# ai_esp12e_aerial.net
KiCad netlist of a schematic drawn in EAGLE
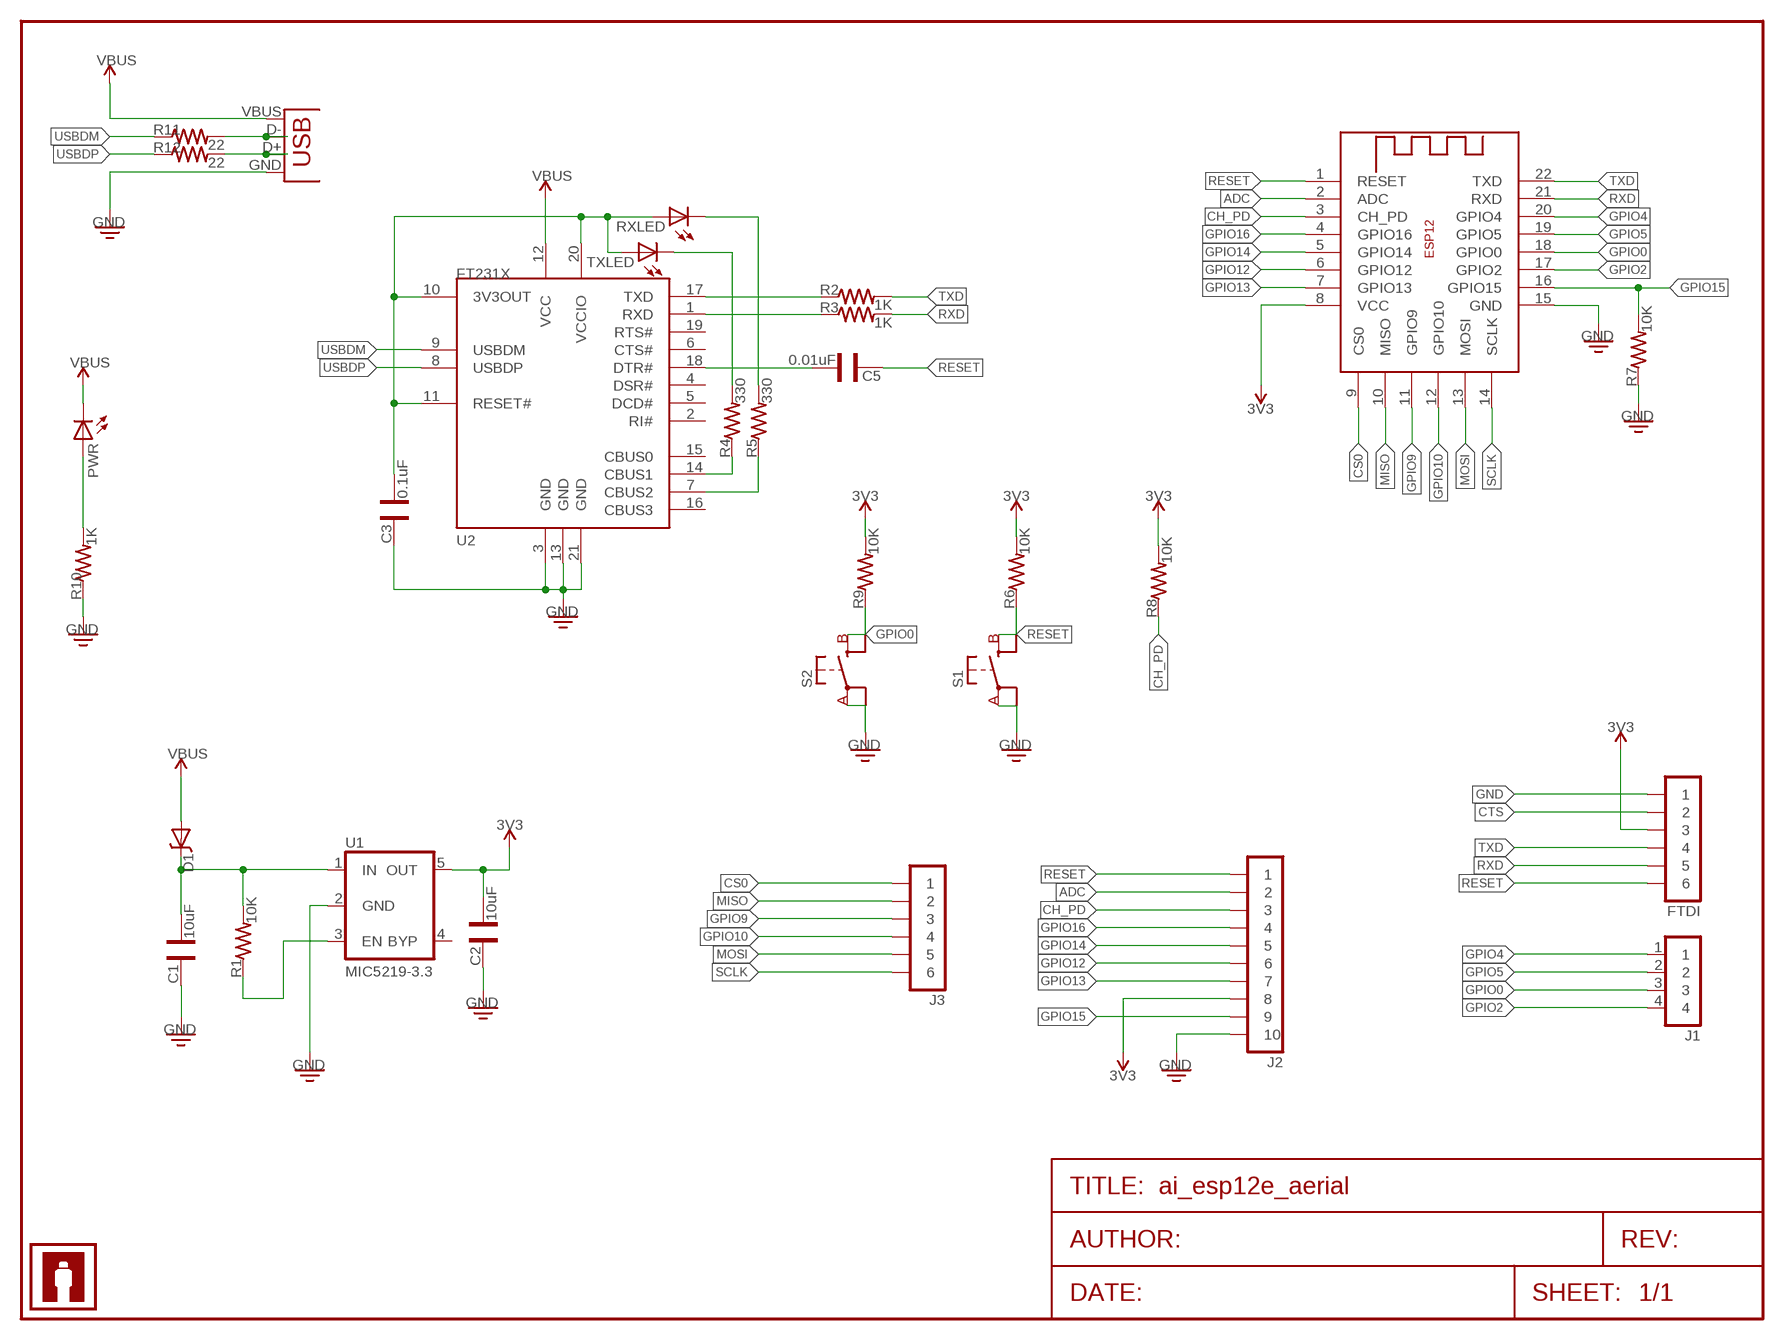
[diagram p0: schematic, sheet 1]

(export (version "E")
  (design (tool "Eeschema 10.0.6"))
  (components
    (comp (ref "C1")
      (value "10uF")
      (footprint "eagle-import:CAP-0603")
      (libsource (lib "eagle-import") (part "CAP0603"))
    )
    (comp (ref "C2")
      (value "10uF")
      (footprint "eagle-import:CAP-0603")
      (libsource (lib "eagle-import") (part "CAP0603"))
    )
    (comp (ref "C3")
      (value "0.1uF")
      (footprint "eagle-import:CAP-0603")
      (libsource (lib "eagle-import") (part "CAP0603"))
    )
    (comp (ref "C5")
      (value "0.01uF")
      (footprint "eagle-import:CAP-0603")
      (libsource (lib "eagle-import") (part "CAP0603"))
    )
    (comp (ref "D1")
      (value "DIODE-SCHOTTKYSOD-523")
      (footprint "eagle-import:SOD-523")
      (libsource (lib "eagle-import") (part "DIODE-SCHOTTKYSOD-523"))
    )
    (comp (ref "FTDI")
      (value "1X06FTDI")
      (footprint "eagle-import:1X06-CUSTOMSP")
      (libsource (lib "eagle-import") (part "1X06FTDI"))
    )
    (comp (ref "J1")
      (value "1X04NFNS")
      (footprint "eagle-import:1X04-NFNS")
      (libsource (lib "eagle-import") (part "1X04NFNS"))
    )
    (comp (ref "J2")
      (value "1X10NFNS")
      (footprint "eagle-import:1X10-NFNS")
      (libsource (lib "eagle-import") (part "1X10NFNS"))
    )
    (comp (ref "J3")
      (value "1X061X06-NFNS")
      (footprint "eagle-import:1X06-NFNS")
      (libsource (lib "eagle-import") (part "1X061X06-NFNS"))
    )
    (comp (ref "PWR")
      (value "LED0603")
      (footprint "eagle-import:LED-0603")
      (libsource (lib "eagle-import") (part "LED0603"))
    )
    (comp (ref "R1")
      (value "10K")
      (footprint "eagle-import:RES-0603")
      (libsource (lib "eagle-import") (part "RES0603"))
    )
    (comp (ref "R2")
      (value "1K")
      (footprint "eagle-import:RES-0603")
      (libsource (lib "eagle-import") (part "RES0603"))
    )
    (comp (ref "R3")
      (value "1K")
      (footprint "eagle-import:RES-0603")
      (libsource (lib "eagle-import") (part "RES0603"))
    )
    (comp (ref "R4")
      (value "330")
      (footprint "eagle-import:RES-0603")
      (libsource (lib "eagle-import") (part "RES0603"))
    )
    (comp (ref "R5")
      (value "330")
      (footprint "eagle-import:RES-0603")
      (libsource (lib "eagle-import") (part "RES0603"))
    )
    (comp (ref "R6")
      (value "10K")
      (footprint "eagle-import:RES-0603")
      (libsource (lib "eagle-import") (part "RES0603"))
    )
    (comp (ref "R7")
      (value "10K")
      (footprint "eagle-import:RES-0603")
      (libsource (lib "eagle-import") (part "RES0603"))
    )
    (comp (ref "R8")
      (value "10K")
      (footprint "eagle-import:RES-0603")
      (libsource (lib "eagle-import") (part "RES0603"))
    )
    (comp (ref "R9")
      (value "10K")
      (footprint "eagle-import:RES-0603")
      (libsource (lib "eagle-import") (part "RES0603"))
    )
    (comp (ref "R10")
      (value "1K")
      (footprint "eagle-import:RES-0603")
      (libsource (lib "eagle-import") (part "RES0603"))
    )
    (comp (ref "R11")
      (value "22")
      (footprint "eagle-import:RES-0603")
      (libsource (lib "eagle-import") (part "RES0603"))
    )
    (comp (ref "R12")
      (value "22")
      (footprint "eagle-import:RES-0603")
      (libsource (lib "eagle-import") (part "RES0603"))
    )
    (comp (ref "RXLED")
      (value "LED0603")
      (footprint "eagle-import:LED-0603")
      (libsource (lib "eagle-import") (part "LED0603"))
    )
    (comp (ref "S1")
      (value "SW-SPSTSMD06X035")
      (footprint "eagle-import:SW-SPST-SMD06X-035")
      (libsource (lib "eagle-import") (part "SW-SPSTSMD06X035"))
    )
    (comp (ref "S2")
      (value "SW-SPSTSMD06X035")
      (footprint "eagle-import:SW-SPST-SMD06X-035")
      (libsource (lib "eagle-import") (part "SW-SPSTSMD06X035"))
    )
    (comp (ref "TXLED")
      (value "LED0603")
      (footprint "eagle-import:LED-0603")
      (libsource (lib "eagle-import") (part "LED0603"))
    )
    (comp (ref "U$1")
      (value "AI-LOGOXS")
      (footprint "eagle-import:AI-LOGO-XS")
      (libsource (lib "eagle-import") (part "AI-LOGOXS"))
    )
    (comp (ref "U1")
      (value "MIC5219-3.3")
      (footprint "eagle-import:SOT23-5")
      (libsource (lib "eagle-import") (part "MIC5219-3.3"))
    )
    (comp (ref "U2")
      (value "FT231X-Q")
      (footprint "eagle-import:QFN20")
      (libsource (lib "eagle-import") (part "FT231X-Q"))
    )
    (comp (ref "USB1")
      (value "USBMICROB-TH")
      (footprint "eagle-import:USB-MICROB-TH")
      (libsource (lib "eagle-import") (part "USBMICROB-TH"))
    )
    (comp (ref "X1")
      (value "ESP-12")
      (footprint "eagle-import:ESP-12")
      (libsource (lib "eagle-import") (part "ESP-12"))
    )
  )
  (nets
    (net (code "1") (name "3V3") (class "Default")
      (node (ref "C2") (pin "1") (pinfunction "1_1") (pintype "passive"))
      (node (ref "FTDI") (pin "3") (pinfunction "3_3") (pintype "bidirectional"))
      (node (ref "J2") (pin "8") (pinfunction "8_8") (pintype "bidirectional"))
      (node (ref "R6") (pin "2") (pinfunction "2_2") (pintype "passive"))
      (node (ref "R8") (pin "2") (pinfunction "2_2") (pintype "passive"))
      (node (ref "R9") (pin "2") (pinfunction "2_2") (pintype "passive"))
      (node (ref "U1") (pin "5") (pinfunction "OUT_5") (pintype "passive"))
      (node (ref "X1") (pin "8") (pinfunction "VCC_8") (pintype "power_in"))
    )
    (net (code "2") (name "ADC") (class "Default")
      (node (ref "J2") (pin "2") (pinfunction "2_2") (pintype "bidirectional"))
      (node (ref "X1") (pin "2") (pinfunction "ADC_2") (pintype "passive"))
    )
    (net (code "3") (name "CH_PD") (class "Default")
      (node (ref "J2") (pin "3") (pinfunction "3_3") (pintype "bidirectional"))
      (node (ref "R8") (pin "1") (pinfunction "1_1") (pintype "passive"))
      (node (ref "X1") (pin "3") (pinfunction "CH_PD_3") (pintype "input"))
    )
    (net (code "4") (name "CS0") (class "Default")
      (node (ref "J3") (pin "1") (pinfunction "1_1") (pintype "bidirectional"))
      (node (ref "X1") (pin "9") (pinfunction "CS0_9") (pintype "bidirectional"))
    )
    (net (code "5") (name "CTS") (class "Default")
      (node (ref "FTDI") (pin "2") (pinfunction "2_2") (pintype "bidirectional"))
    )
    (net (code "6") (name "GND") (class "Default")
      (node (ref "C1") (pin "2") (pinfunction "2_2") (pintype "passive"))
      (node (ref "C2") (pin "2") (pinfunction "2_2") (pintype "passive"))
      (node (ref "C3") (pin "2") (pinfunction "2_2") (pintype "passive"))
      (node (ref "FTDI") (pin "1") (pinfunction "1_1") (pintype "bidirectional"))
      (node (ref "J2") (pin "10") (pinfunction "10_10") (pintype "bidirectional"))
      (node (ref "R10") (pin "1") (pinfunction "1_1") (pintype "passive"))
      (node (ref "R7") (pin "1") (pinfunction "1_1") (pintype "passive"))
      (node (ref "S1") (pin "P$1") (pinfunction "A_P$1") (pintype "passive"))
      (node (ref "S2") (pin "P$1") (pinfunction "A_P$1") (pintype "passive"))
      (node (ref "U1") (pin "2") (pinfunction "GND_2") (pintype "input"))
      (node (ref "U2") (pin "13") (pinfunction "GND_13") (pintype "bidirectional"))
      (node (ref "U2") (pin "21") (pinfunction "GND_21") (pintype "bidirectional"))
      (node (ref "U2") (pin "3") (pinfunction "GND_3") (pintype "bidirectional"))
      (node (ref "USB1") (pin "GND") (pinfunction "GND_GND") (pintype "bidirectional"))
      (node (ref "X1") (pin "15") (pinfunction "GND_15") (pintype "power_in"))
    )
    (net (code "7") (name "GPIO0") (class "Default")
      (node (ref "J1") (pin "3") (pinfunction "3_3") (pintype "bidirectional"))
      (node (ref "R9") (pin "1") (pinfunction "1_1") (pintype "passive"))
      (node (ref "S2") (pin "P$2") (pinfunction "B_P$2") (pintype "passive"))
      (node (ref "X1") (pin "18") (pinfunction "GPIO0_18") (pintype "bidirectional"))
    )
    (net (code "8") (name "GPIO2") (class "Default")
      (node (ref "J1") (pin "4") (pinfunction "4_4") (pintype "bidirectional"))
      (node (ref "X1") (pin "17") (pinfunction "GPIO2_17") (pintype "bidirectional"))
    )
    (net (code "9") (name "GPIO4") (class "Default")
      (node (ref "J1") (pin "1") (pinfunction "1_1") (pintype "bidirectional"))
      (node (ref "X1") (pin "20") (pinfunction "GPIO4_20") (pintype "bidirectional"))
    )
    (net (code "10") (name "GPIO5") (class "Default")
      (node (ref "J1") (pin "2") (pinfunction "2_2") (pintype "bidirectional"))
      (node (ref "X1") (pin "19") (pinfunction "GPIO5_19") (pintype "bidirectional"))
    )
    (net (code "11") (name "GPIO9") (class "Default")
      (node (ref "J3") (pin "3") (pinfunction "3_3") (pintype "bidirectional"))
      (node (ref "X1") (pin "11") (pinfunction "GPIO9_11") (pintype "bidirectional"))
    )
    (net (code "12") (name "GPIO10") (class "Default")
      (node (ref "J3") (pin "4") (pinfunction "4_4") (pintype "bidirectional"))
      (node (ref "X1") (pin "12") (pinfunction "GPIO10_12") (pintype "bidirectional"))
    )
    (net (code "13") (name "GPIO12") (class "Default")
      (node (ref "J2") (pin "6") (pinfunction "6_6") (pintype "bidirectional"))
      (node (ref "X1") (pin "6") (pinfunction "GPIO12_6") (pintype "bidirectional"))
    )
    (net (code "14") (name "GPIO13") (class "Default")
      (node (ref "J2") (pin "7") (pinfunction "7_7") (pintype "bidirectional"))
      (node (ref "X1") (pin "7") (pinfunction "GPIO13_7") (pintype "bidirectional"))
    )
    (net (code "15") (name "GPIO14") (class "Default")
      (node (ref "J2") (pin "5") (pinfunction "5_5") (pintype "bidirectional"))
      (node (ref "X1") (pin "5") (pinfunction "GPIO14_5") (pintype "bidirectional"))
    )
    (net (code "16") (name "GPIO15") (class "Default")
      (node (ref "J2") (pin "9") (pinfunction "9_9") (pintype "bidirectional"))
      (node (ref "R7") (pin "2") (pinfunction "2_2") (pintype "passive"))
      (node (ref "X1") (pin "16") (pinfunction "GPIO15_16") (pintype "bidirectional"))
    )
    (net (code "17") (name "GPIO16") (class "Default")
      (node (ref "J2") (pin "4") (pinfunction "4_4") (pintype "bidirectional"))
      (node (ref "X1") (pin "4") (pinfunction "GPIO16_4") (pintype "bidirectional"))
    )
    (net (code "18") (name "MISO") (class "Default")
      (node (ref "J3") (pin "2") (pinfunction "2_2") (pintype "bidirectional"))
      (node (ref "X1") (pin "10") (pinfunction "MISO_10") (pintype "bidirectional"))
    )
    (net (code "19") (name "MOSI") (class "Default")
      (node (ref "J3") (pin "5") (pinfunction "5_5") (pintype "bidirectional"))
      (node (ref "X1") (pin "13") (pinfunction "MOSI_13") (pintype "bidirectional"))
    )
    (net (code "20") (name "Net-(PWR-PadA)") (class "Default")
      (node (ref "PWR") (pin "A") (pinfunction "A_A") (pintype "passive"))
      (node (ref "R10") (pin "2") (pinfunction "2_2") (pintype "passive"))
    )
    (net (code "21") (name "Net-(R4-Pad2)") (class "Default")
      (node (ref "R4") (pin "2") (pinfunction "2_2") (pintype "passive"))
      (node (ref "TXLED") (pin "C") (pinfunction "C_C") (pintype "passive"))
    )
    (net (code "22") (name "Net-(R5-Pad2)") (class "Default")
      (node (ref "R5") (pin "2") (pinfunction "2_2") (pintype "passive"))
      (node (ref "RXLED") (pin "C") (pinfunction "C_C") (pintype "passive"))
    )
    (net (code "23") (name "Net-(R11-Pad2)") (class "Default")
      (node (ref "R11") (pin "2") (pinfunction "2_2") (pintype "passive"))
      (node (ref "USB1") (pin "D-") (pinfunction "D-_D-") (pintype "bidirectional"))
    )
    (net (code "24") (name "Net-(R12-Pad2)") (class "Default")
      (node (ref "R12") (pin "2") (pinfunction "2_2") (pintype "passive"))
      (node (ref "USB1") (pin "D+") (pinfunction "D+_D+") (pintype "bidirectional"))
    )
    (net (code "25") (name "Net-(U1-EN)") (class "Default")
      (node (ref "R1") (pin "1") (pinfunction "1_1") (pintype "passive"))
      (node (ref "U1") (pin "3") (pinfunction "EN_3") (pintype "input"))
    )
    (net (code "26") (name "Net-(U1-IN)") (class "Default")
      (node (ref "C1") (pin "1") (pinfunction "1_1") (pintype "passive"))
      (node (ref "D1") (pin "C") (pinfunction "C_C") (pintype "passive"))
      (node (ref "R1") (pin "2") (pinfunction "2_2") (pintype "passive"))
      (node (ref "U1") (pin "1") (pinfunction "IN_1") (pintype "input"))
    )
    (net (code "27") (name "Net-(U2-3V3OUT)") (class "Default")
      (node (ref "C3") (pin "1") (pinfunction "1_1") (pintype "passive"))
      (node (ref "RXLED") (pin "A") (pinfunction "A_A") (pintype "passive"))
      (node (ref "TXLED") (pin "A") (pinfunction "A_A") (pintype "passive"))
      (node (ref "U2") (pin "10") (pinfunction "3V3OUT_10") (pintype "bidirectional"))
      (node (ref "U2") (pin "11") (pinfunction "RESET#_11") (pintype "bidirectional"))
      (node (ref "U2") (pin "20") (pinfunction "VCCIO_20") (pintype "bidirectional"))
    )
    (net (code "28") (name "Net-(U2-CBUS1)") (class "Default")
      (node (ref "R4") (pin "1") (pinfunction "1_1") (pintype "passive"))
      (node (ref "U2") (pin "14") (pinfunction "CBUS1_14") (pintype "bidirectional"))
    )
    (net (code "29") (name "Net-(U2-CBUS2)") (class "Default")
      (node (ref "R5") (pin "1") (pinfunction "1_1") (pintype "passive"))
      (node (ref "U2") (pin "7") (pinfunction "CBUS2_7") (pintype "bidirectional"))
    )
    (net (code "30") (name "Net-(U2-DTR#)") (class "Default")
      (node (ref "C5") (pin "1") (pinfunction "1_1") (pintype "passive"))
      (node (ref "U2") (pin "18") (pinfunction "DTR#_18") (pintype "bidirectional"))
    )
    (net (code "31") (name "Net-(U2-RXD)") (class "Default")
      (node (ref "R3") (pin "1") (pinfunction "1_1") (pintype "passive"))
      (node (ref "U2") (pin "1") (pinfunction "RXD_1") (pintype "bidirectional"))
    )
    (net (code "32") (name "Net-(U2-TXD)") (class "Default")
      (node (ref "R2") (pin "1") (pinfunction "1_1") (pintype "passive"))
      (node (ref "U2") (pin "17") (pinfunction "TXD_17") (pintype "bidirectional"))
    )
    (net (code "33") (name "RESET") (class "Default")
      (node (ref "C5") (pin "2") (pinfunction "2_2") (pintype "passive"))
      (node (ref "FTDI") (pin "6") (pinfunction "6_6") (pintype "bidirectional"))
      (node (ref "J2") (pin "1") (pinfunction "1_1") (pintype "bidirectional"))
      (node (ref "R6") (pin "1") (pinfunction "1_1") (pintype "passive"))
      (node (ref "S1") (pin "P$2") (pinfunction "B_P$2") (pintype "passive"))
      (node (ref "X1") (pin "1") (pinfunction "RESET_1") (pintype "input"))
    )
    (net (code "34") (name "RXD") (class "Default")
      (node (ref "FTDI") (pin "5") (pinfunction "5_5") (pintype "bidirectional"))
      (node (ref "R3") (pin "2") (pinfunction "2_2") (pintype "passive"))
      (node (ref "X1") (pin "21") (pinfunction "RXD_21") (pintype "input"))
    )
    (net (code "35") (name "SCLK") (class "Default")
      (node (ref "J3") (pin "6") (pinfunction "6_6") (pintype "bidirectional"))
      (node (ref "X1") (pin "14") (pinfunction "SCLK_14") (pintype "bidirectional"))
    )
    (net (code "36") (name "TXD") (class "Default")
      (node (ref "FTDI") (pin "4") (pinfunction "4_4") (pintype "bidirectional"))
      (node (ref "R2") (pin "2") (pinfunction "2_2") (pintype "passive"))
      (node (ref "X1") (pin "22") (pinfunction "TXD_22") (pintype "output"))
    )
    (net (code "37") (name "USBDM") (class "Default")
      (node (ref "R11") (pin "1") (pinfunction "1_1") (pintype "passive"))
      (node (ref "U2") (pin "9") (pinfunction "USBDM_9") (pintype "bidirectional"))
    )
    (net (code "38") (name "USBDP") (class "Default")
      (node (ref "R12") (pin "1") (pinfunction "1_1") (pintype "passive"))
      (node (ref "U2") (pin "8") (pinfunction "USBDP_8") (pintype "bidirectional"))
    )
    (net (code "39") (name "VBUS") (class "Default")
      (node (ref "D1") (pin "A") (pinfunction "A_A") (pintype "passive"))
      (node (ref "PWR") (pin "C") (pinfunction "C_C") (pintype "passive"))
      (node (ref "U2") (pin "12") (pinfunction "VCC_12") (pintype "bidirectional"))
      (node (ref "USB1") (pin "VBUS") (pinfunction "VBUS_VBUS") (pintype "bidirectional"))
    )
    (net (code "40") (name "unconnected-(U1-BYP-Pad4)") (class "Default")
      (node (ref "U1") (pin "4") (pinfunction "BYP_4") (pintype "input"))
    )
    (net (code "41") (name "unconnected-(U2-CBUS0-Pad15)") (class "Default")
      (node (ref "U2") (pin "15") (pinfunction "CBUS0_15") (pintype "bidirectional"))
    )
    (net (code "42") (name "unconnected-(U2-CBUS3-Pad16)") (class "Default")
      (node (ref "U2") (pin "16") (pinfunction "CBUS3_16") (pintype "bidirectional"))
    )
    (net (code "43") (name "unconnected-(U2-CTS#-Pad6)") (class "Default")
      (node (ref "U2") (pin "6") (pinfunction "CTS#_6") (pintype "bidirectional"))
    )
    (net (code "44") (name "unconnected-(U2-DCD#-Pad5)") (class "Default")
      (node (ref "U2") (pin "5") (pinfunction "DCD#_5") (pintype "bidirectional"))
    )
    (net (code "45") (name "unconnected-(U2-DSR#-Pad4)") (class "Default")
      (node (ref "U2") (pin "4") (pinfunction "DSR#_4") (pintype "bidirectional"))
    )
    (net (code "46") (name "unconnected-(U2-RI#-Pad2)") (class "Default")
      (node (ref "U2") (pin "2") (pinfunction "RI#_2") (pintype "bidirectional"))
    )
    (net (code "47") (name "unconnected-(U2-RTS#-Pad19)") (class "Default")
      (node (ref "U2") (pin "19") (pinfunction "RTS#_19") (pintype "bidirectional"))
    )
  )
)
